# STM32_POWER.net
KiCad netlist of a schematic drawn in Altium Designer
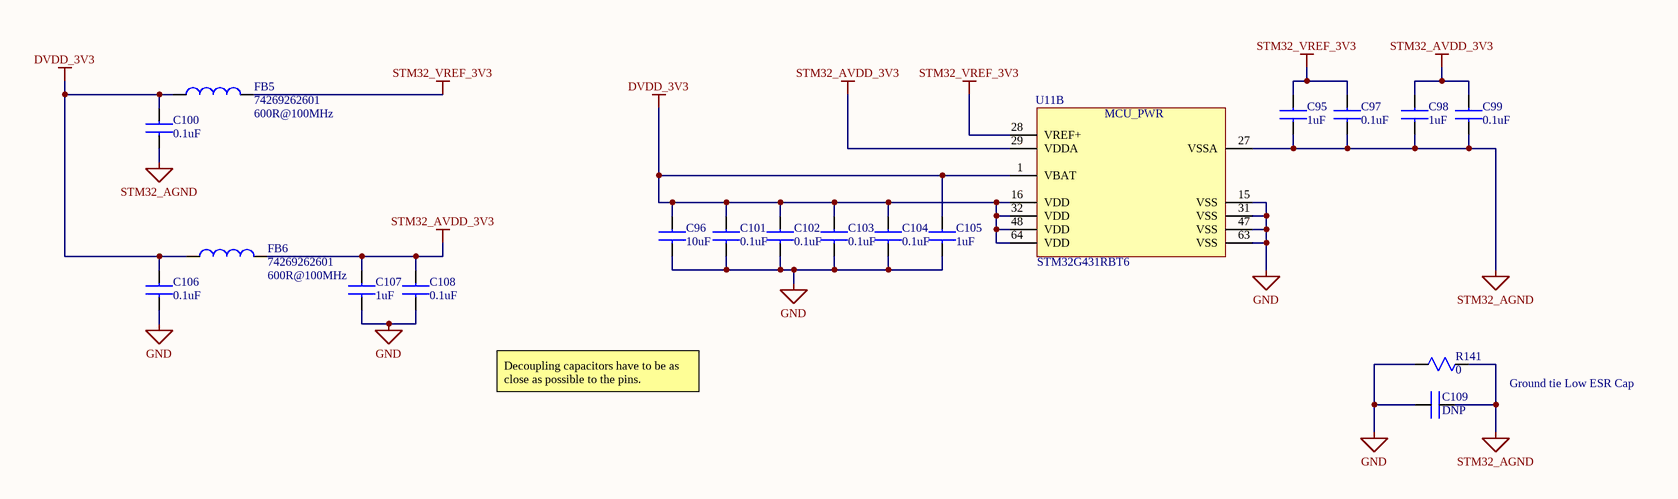
[diagram p0: STM32_POWER.SchDoc]

(export (version "E")
  (design (tool "Eeschema 10.0.6"))
  (components
    (comp (ref "C95")
      (value "1uF")
      (footprint "0603")
      (description "CAP CER 1UF 50V X7R 0603")
      (fields (field (name "MFG") "YAGEO"))
      (libsource (lib "Myomo_SCH_Library") (part "C_0603_CER_1uF_50V_X7R"))
    )
    (comp (ref "C96")
      (value "10uF")
      (footprint "1210")
      (description "CAP CER 10UF 25V X7R 1210")
      (fields (field (name "MFG") "SUMSUNG"))
      (libsource (lib "Myomo_SCH_Library") (part "C_1210_CER_10uF_25V_X7R"))
    )
    (comp (ref "C97")
      (value "0.1uF")
      (footprint "0402")
      (description "CAP CER 0.1UF 50V X7R 0402")
      (fields (field (name "MFG") "Samsung"))
      (libsource (lib "Myomo_SCH_Library") (part "C_0402_CER_0.1uF_50V_X7R"))
    )
    (comp (ref "C98")
      (value "1uF")
      (footprint "0603")
      (description "CAP CER 1UF 50V X7R 0603")
      (fields (field (name "MFG") "YAGEO"))
      (libsource (lib "Myomo_SCH_Library") (part "C_0603_CER_1uF_50V_X7R"))
    )
    (comp (ref "C99")
      (value "0.1uF")
      (footprint "0402")
      (description "CAP CER 0.1UF 50V X7R 0402")
      (fields (field (name "MFG") "Samsung"))
      (libsource (lib "Myomo_SCH_Library") (part "C_0402_CER_0.1uF_50V_X7R"))
    )
    (comp (ref "C100")
      (value "0.1uF")
      (footprint "0402")
      (description "CAP CER 0.1UF 50V X7R 0402")
      (fields (field (name "MFG") "Samsung"))
      (libsource (lib "Myomo_SCH_Library") (part "C_0402_CER_0.1uF_50V_X7R"))
    )
    (comp (ref "C101")
      (value "0.1uF")
      (footprint "0402")
      (description "CAP CER 0.1UF 50V X7R 0402")
      (fields (field (name "MFG") "Samsung"))
      (libsource (lib "Myomo_SCH_Library") (part "C_0402_CER_0.1uF_50V_X7R"))
    )
    (comp (ref "C102")
      (value "0.1uF")
      (footprint "0402")
      (description "CAP CER 0.1UF 50V X7R 0402")
      (fields (field (name "MFG") "Samsung"))
      (libsource (lib "Myomo_SCH_Library") (part "C_0402_CER_0.1uF_50V_X7R"))
    )
    (comp (ref "C103")
      (value "0.1uF")
      (footprint "0402")
      (description "CAP CER 0.1UF 50V X7R 0402")
      (fields (field (name "MFG") "Samsung"))
      (libsource (lib "Myomo_SCH_Library") (part "C_0402_CER_0.1uF_50V_X7R"))
    )
    (comp (ref "C104")
      (value "0.1uF")
      (footprint "0402")
      (description "CAP CER 0.1UF 50V X7R 0402")
      (fields (field (name "MFG") "Samsung"))
      (libsource (lib "Myomo_SCH_Library") (part "C_0402_CER_0.1uF_50V_X7R"))
    )
    (comp (ref "C105")
      (value "1uF")
      (footprint "0603")
      (description "CAP CER 1UF 50V X7R 0603")
      (fields (field (name "MFG") "YAGEO"))
      (libsource (lib "Myomo_SCH_Library") (part "C_0603_CER_1uF_50V_X7R"))
    )
    (comp (ref "C106")
      (value "0.1uF")
      (footprint "0402")
      (description "CAP CER 0.1UF 50V X7R 0402")
      (fields (field (name "MFG") "Samsung"))
      (libsource (lib "Myomo_SCH_Library") (part "C_0402_CER_0.1uF_50V_X7R"))
    )
    (comp (ref "C107")
      (value "1uF")
      (footprint "0603")
      (description "CAP CER 1UF 50V X7R 0603")
      (fields (field (name "MFG") "YAGEO"))
      (libsource (lib "Myomo_SCH_Library") (part "C_0603_CER_1uF_50V_X7R"))
    )
    (comp (ref "C108")
      (value "0.1uF")
      (footprint "0402")
      (description "CAP CER 0.1UF 50V X7R 0402")
      (fields (field (name "MFG") "Samsung"))
      (libsource (lib "Myomo_SCH_Library") (part "C_0402_CER_0.1uF_50V_X7R"))
    )
    (comp (ref "C109")
      (value "DNP")
      (footprint "0603")
      (description "CAP CER 0603 DNP")
      (libsource (lib "Myomo_SCH_Library") (part "C_0603_DNP"))
    )
    (comp (ref "FB5")
      (value "74269262601")
      (footprint "0603")
      (description "600 Ohms @ 100 MHz 1 Power Line Ferrite Bead 0603 (1608 Metric) 1.5A 100mOhm")
      (fields (field (name "MFG") "Wurth Elektronik"))
      (libsource (lib "Myomo_SCH_Library") (part "FB_0603 _600_100MHz_1.5A"))
    )
    (comp (ref "FB6")
      (value "74269262601")
      (footprint "0603")
      (description "600 Ohms @ 100 MHz 1 Power Line Ferrite Bead 0603 (1608 Metric) 1.5A 100mOhm")
      (fields (field (name "MFG") "Wurth Elektronik"))
      (libsource (lib "Myomo_SCH_Library") (part "FB_0603 _600_100MHz_1.5A"))
    )
    (comp (ref "R141")
      (value "0")
      (footprint "0603")
      (description "RES 0 OHM JUMPER 1/10W 0603")
      (fields (field (name "MFG") "YAGEO"))
      (libsource (lib "Myomo_SCH_Library") (part "R_0603_0"))
    )
    (comp (ref "U11")
      (value "STM32G431RBT6")
      (footprint "U_STM32G431R")
      (description "STM32G431, LQFP64 package")
      (fields (field (name "MFG") "STMicroelectronics"))
      (libsource (lib "Myomo_SCH_Library") (part "U_STM32G431R"))
    )
  )
  (nets
    (net (code "1") (name "DVDD_3V3") (class "Default")
      (node (ref "C100") (pin "1") (pinfunction "1_1") (pintype "passive"))
      (node (ref "C101") (pin "1") (pinfunction "1_1") (pintype "passive"))
      (node (ref "C102") (pin "1") (pinfunction "1_1") (pintype "passive"))
      (node (ref "C103") (pin "1") (pinfunction "1_1") (pintype "passive"))
      (node (ref "C104") (pin "1") (pinfunction "1_1") (pintype "passive"))
      (node (ref "C105") (pin "1") (pinfunction "1_1") (pintype "passive"))
      (node (ref "C106") (pin "1") (pinfunction "1_1") (pintype "passive"))
      (node (ref "C96") (pin "1") (pinfunction "1_1") (pintype "passive"))
      (node (ref "FB5") (pin "1") (pinfunction "1_1") (pintype "passive"))
      (node (ref "FB6") (pin "1") (pinfunction "1_1") (pintype "passive"))
      (node (ref "U11") (pin "1") (pinfunction "VBAT_1") (pintype "passive"))
      (node (ref "U11") (pin "16") (pinfunction "VDD_16") (pintype "passive"))
      (node (ref "U11") (pin "32") (pinfunction "VDD_32") (pintype "passive"))
      (node (ref "U11") (pin "48") (pinfunction "VDD_48") (pintype "passive"))
      (node (ref "U11") (pin "64") (pinfunction "VDD_64") (pintype "passive"))
    )
    (net (code "2") (name "GND") (class "Default")
      (node (ref "C101") (pin "2") (pinfunction "2_2") (pintype "passive"))
      (node (ref "C102") (pin "2") (pinfunction "2_2") (pintype "passive"))
      (node (ref "C103") (pin "2") (pinfunction "2_2") (pintype "passive"))
      (node (ref "C104") (pin "2") (pinfunction "2_2") (pintype "passive"))
      (node (ref "C105") (pin "2") (pinfunction "2_2") (pintype "passive"))
      (node (ref "C106") (pin "2") (pinfunction "2_2") (pintype "passive"))
      (node (ref "C107") (pin "2") (pinfunction "2_2") (pintype "passive"))
      (node (ref "C108") (pin "2") (pinfunction "2_2") (pintype "passive"))
      (node (ref "C109") (pin "1") (pinfunction "1_1") (pintype "passive"))
      (node (ref "C96") (pin "2") (pinfunction "2_2") (pintype "passive"))
      (node (ref "R141") (pin "1") (pinfunction "1_1") (pintype "passive"))
      (node (ref "U11") (pin "15") (pinfunction "VSS_15") (pintype "passive"))
      (node (ref "U11") (pin "31") (pinfunction "VSS_31") (pintype "passive"))
      (node (ref "U11") (pin "47") (pinfunction "VSS_47") (pintype "passive"))
      (node (ref "U11") (pin "63") (pinfunction "VSS_63") (pintype "passive"))
    )
    (net (code "3") (name "STM32_AGND") (class "Default")
      (node (ref "C100") (pin "2") (pinfunction "2_2") (pintype "passive"))
      (node (ref "C109") (pin "2") (pinfunction "2_2") (pintype "passive"))
      (node (ref "C95") (pin "2") (pinfunction "2_2") (pintype "passive"))
      (node (ref "C97") (pin "2") (pinfunction "2_2") (pintype "passive"))
      (node (ref "C98") (pin "2") (pinfunction "2_2") (pintype "passive"))
      (node (ref "C99") (pin "2") (pinfunction "2_2") (pintype "passive"))
      (node (ref "R141") (pin "2") (pinfunction "2_2") (pintype "passive"))
      (node (ref "U11") (pin "27") (pinfunction "VSSA_27") (pintype "passive"))
    )
    (net (code "4") (name "STM32_AVDD_3V3") (class "Default")
      (node (ref "C107") (pin "1") (pinfunction "1_1") (pintype "passive"))
      (node (ref "C108") (pin "1") (pinfunction "1_1") (pintype "passive"))
      (node (ref "C98") (pin "1") (pinfunction "1_1") (pintype "passive"))
      (node (ref "C99") (pin "1") (pinfunction "1_1") (pintype "passive"))
      (node (ref "FB6") (pin "2") (pinfunction "2_2") (pintype "passive"))
      (node (ref "U11") (pin "29") (pinfunction "VDDA_29") (pintype "passive"))
    )
    (net (code "5") (name "STM32_VREF_3V3") (class "Default")
      (node (ref "C95") (pin "1") (pinfunction "1_1") (pintype "passive"))
      (node (ref "C97") (pin "1") (pinfunction "1_1") (pintype "passive"))
      (node (ref "FB5") (pin "2") (pinfunction "2_2") (pintype "passive"))
      (node (ref "U11") (pin "28") (pinfunction "VREF+_28") (pintype "passive"))
    )
  )
)
